# DSP_GPIO_Part4.net
KiCad netlist of a schematic drawn in Altium Designer
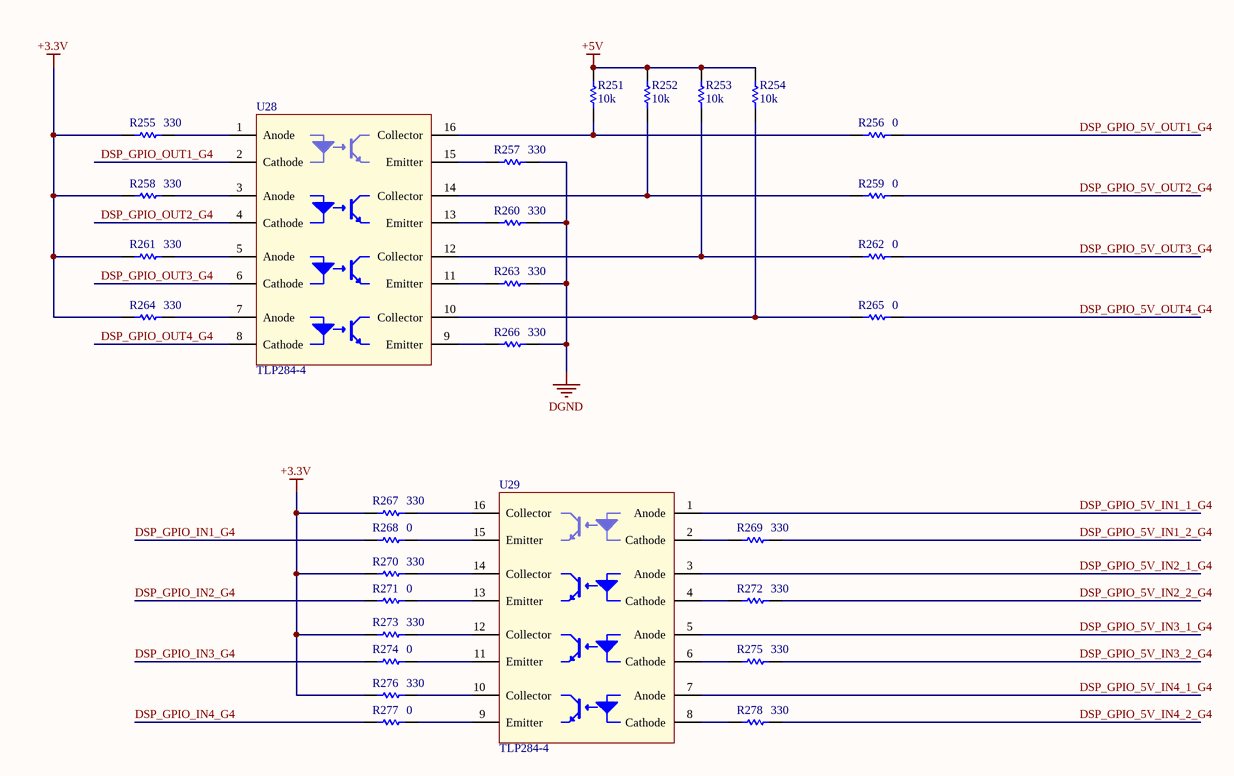
[diagram p0: DSP_GPIO_Part4.SchDoc]

(export (version "E")
  (design (tool "Eeschema 10.0.6"))
  (components
    (comp (ref "R251")
      (value "10k")
      (footprint "1608[0603]")
      (description "Resistor")
      (fields (field (name "Comment") "Res1") (field (name "PUBLISHER") "Altium Limited"))
      (libsource (lib "Miscellaneous Devices") (part "Res1"))
    )
    (comp (ref "R252")
      (value "10k")
      (footprint "1608[0603]")
      (description "Resistor")
      (fields (field (name "Comment") "Res1") (field (name "PUBLISHER") "Altium Limited"))
      (libsource (lib "Miscellaneous Devices") (part "Res1"))
    )
    (comp (ref "R253")
      (value "10k")
      (footprint "1608[0603]")
      (description "Resistor")
      (fields (field (name "Comment") "Res1") (field (name "PUBLISHER") "Altium Limited"))
      (libsource (lib "Miscellaneous Devices") (part "Res1"))
    )
    (comp (ref "R254")
      (value "10k")
      (footprint "1608[0603]")
      (description "Resistor")
      (fields (field (name "Comment") "Res1") (field (name "PUBLISHER") "Altium Limited"))
      (libsource (lib "Miscellaneous Devices") (part "Res1"))
    )
    (comp (ref "R255")
      (value "330")
      (footprint "1608[0603]")
      (description "Resistor")
      (fields (field (name "Comment") "Res1") (field (name "PUBLISHER") "Altium Limited"))
      (libsource (lib "Miscellaneous Devices") (part "Res1"))
    )
    (comp (ref "R256")
      (value "0")
      (footprint "1608[0603]")
      (description "Resistor")
      (fields (field (name "Comment") "Res1") (field (name "PUBLISHER") "Altium Limited"))
      (libsource (lib "Miscellaneous Devices") (part "Res1"))
    )
    (comp (ref "R257")
      (value "330")
      (footprint "1608[0603]")
      (description "Resistor")
      (fields (field (name "Comment") "Res1") (field (name "PUBLISHER") "Altium Limited"))
      (libsource (lib "Miscellaneous Devices") (part "Res1"))
    )
    (comp (ref "R258")
      (value "330")
      (footprint "1608[0603]")
      (description "Resistor")
      (fields (field (name "Comment") "Res1") (field (name "PUBLISHER") "Altium Limited"))
      (libsource (lib "Miscellaneous Devices") (part "Res1"))
    )
    (comp (ref "R259")
      (value "0")
      (footprint "1608[0603]")
      (description "Resistor")
      (fields (field (name "Comment") "Res1") (field (name "PUBLISHER") "Altium Limited"))
      (libsource (lib "Miscellaneous Devices") (part "Res1"))
    )
    (comp (ref "R260")
      (value "330")
      (footprint "1608[0603]")
      (description "Resistor")
      (fields (field (name "Comment") "Res1") (field (name "PUBLISHER") "Altium Limited"))
      (libsource (lib "Miscellaneous Devices") (part "Res1"))
    )
    (comp (ref "R261")
      (value "330")
      (footprint "1608[0603]")
      (description "Resistor")
      (fields (field (name "Comment") "Res1") (field (name "PUBLISHER") "Altium Limited"))
      (libsource (lib "Miscellaneous Devices") (part "Res1"))
    )
    (comp (ref "R262")
      (value "0")
      (footprint "1608[0603]")
      (description "Resistor")
      (fields (field (name "Comment") "Res1") (field (name "PUBLISHER") "Altium Limited"))
      (libsource (lib "Miscellaneous Devices") (part "Res1"))
    )
    (comp (ref "R263")
      (value "330")
      (footprint "1608[0603]")
      (description "Resistor")
      (fields (field (name "Comment") "Res1") (field (name "PUBLISHER") "Altium Limited"))
      (libsource (lib "Miscellaneous Devices") (part "Res1"))
    )
    (comp (ref "R264")
      (value "330")
      (footprint "1608[0603]")
      (description "Resistor")
      (fields (field (name "Comment") "Res1") (field (name "PUBLISHER") "Altium Limited"))
      (libsource (lib "Miscellaneous Devices") (part "Res1"))
    )
    (comp (ref "R265")
      (value "0")
      (footprint "1608[0603]")
      (description "Resistor")
      (fields (field (name "Comment") "Res1") (field (name "PUBLISHER") "Altium Limited"))
      (libsource (lib "Miscellaneous Devices") (part "Res1"))
    )
    (comp (ref "R266")
      (value "330")
      (footprint "1608[0603]")
      (description "Resistor")
      (fields (field (name "Comment") "Res1") (field (name "PUBLISHER") "Altium Limited"))
      (libsource (lib "Miscellaneous Devices") (part "Res1"))
    )
    (comp (ref "R267")
      (value "330")
      (footprint "1608[0603]")
      (description "Resistor")
      (fields (field (name "Comment") "Res1") (field (name "PUBLISHER") "Altium Limited"))
      (libsource (lib "Miscellaneous Devices") (part "Res1"))
    )
    (comp (ref "R268")
      (value "0")
      (footprint "1608[0603]")
      (description "Resistor")
      (fields (field (name "Comment") "Res1") (field (name "PUBLISHER") "Altium Limited"))
      (libsource (lib "Miscellaneous Devices") (part "Res1"))
    )
    (comp (ref "R269")
      (value "330")
      (footprint "1608[0603]")
      (description "Resistor")
      (fields (field (name "Comment") "Res1") (field (name "PUBLISHER") "Altium Limited"))
      (libsource (lib "Miscellaneous Devices") (part "Res1"))
    )
    (comp (ref "R270")
      (value "330")
      (footprint "1608[0603]")
      (description "Resistor")
      (fields (field (name "Comment") "Res1") (field (name "PUBLISHER") "Altium Limited"))
      (libsource (lib "Miscellaneous Devices") (part "Res1"))
    )
    (comp (ref "R271")
      (value "0")
      (footprint "1608[0603]")
      (description "Resistor")
      (fields (field (name "Comment") "Res1") (field (name "PUBLISHER") "Altium Limited"))
      (libsource (lib "Miscellaneous Devices") (part "Res1"))
    )
    (comp (ref "R272")
      (value "330")
      (footprint "1608[0603]")
      (description "Resistor")
      (fields (field (name "Comment") "Res1") (field (name "PUBLISHER") "Altium Limited"))
      (libsource (lib "Miscellaneous Devices") (part "Res1"))
    )
    (comp (ref "R273")
      (value "330")
      (footprint "1608[0603]")
      (description "Resistor")
      (fields (field (name "Comment") "Res1") (field (name "PUBLISHER") "Altium Limited"))
      (libsource (lib "Miscellaneous Devices") (part "Res1"))
    )
    (comp (ref "R274")
      (value "0")
      (footprint "1608[0603]")
      (description "Resistor")
      (fields (field (name "Comment") "Res1") (field (name "PUBLISHER") "Altium Limited"))
      (libsource (lib "Miscellaneous Devices") (part "Res1"))
    )
    (comp (ref "R275")
      (value "330")
      (footprint "1608[0603]")
      (description "Resistor")
      (fields (field (name "Comment") "Res1") (field (name "PUBLISHER") "Altium Limited"))
      (libsource (lib "Miscellaneous Devices") (part "Res1"))
    )
    (comp (ref "R276")
      (value "330")
      (footprint "1608[0603]")
      (description "Resistor")
      (fields (field (name "Comment") "Res1") (field (name "PUBLISHER") "Altium Limited"))
      (libsource (lib "Miscellaneous Devices") (part "Res1"))
    )
    (comp (ref "R277")
      (value "0")
      (footprint "1608[0603]")
      (description "Resistor")
      (fields (field (name "Comment") "Res1") (field (name "PUBLISHER") "Altium Limited"))
      (libsource (lib "Miscellaneous Devices") (part "Res1"))
    )
    (comp (ref "R278")
      (value "330")
      (footprint "1608[0603]")
      (description "Resistor")
      (fields (field (name "Comment") "Res1") (field (name "PUBLISHER") "Altium Limited"))
      (libsource (lib "Miscellaneous Devices") (part "Res1"))
    )
    (comp (ref "U28")
      (value "TLP284-4")
      (footprint "TLP284-4")
      (libsource (lib "DSP_FPGA_Lib") (part "TLP284-4"))
    )
    (comp (ref "U29")
      (value "TLP284-4")
      (footprint "TLP284-4")
      (libsource (lib "DSP_FPGA_Lib") (part "TLP284-4"))
    )
  )
  (nets
    (net (code "1") (name "+3.3V") (class "Default")
      (node (ref "R255") (pin "1") (pinfunction "1_1") (pintype "passive"))
      (node (ref "R258") (pin "1") (pinfunction "1_1") (pintype "passive"))
      (node (ref "R261") (pin "1") (pinfunction "1_1") (pintype "passive"))
      (node (ref "R264") (pin "1") (pinfunction "1_1") (pintype "passive"))
      (node (ref "R267") (pin "1") (pinfunction "1_1") (pintype "passive"))
      (node (ref "R270") (pin "1") (pinfunction "1_1") (pintype "passive"))
      (node (ref "R273") (pin "1") (pinfunction "1_1") (pintype "passive"))
      (node (ref "R276") (pin "1") (pinfunction "1_1") (pintype "passive"))
    )
    (net (code "2") (name "+5V") (class "Default")
      (node (ref "R251") (pin "2") (pinfunction "2_2") (pintype "passive"))
      (node (ref "R252") (pin "2") (pinfunction "2_2") (pintype "passive"))
      (node (ref "R253") (pin "2") (pinfunction "2_2") (pintype "passive"))
      (node (ref "R254") (pin "2") (pinfunction "2_2") (pintype "passive"))
    )
    (net (code "3") (name "/DSP_GPIO_5V_IN1_1_G4") (class "Default")
      (node (ref "U29") (pin "1") (pinfunction "Anode_1") (pintype "passive"))
    )
    (net (code "4") (name "/DSP_GPIO_5V_IN1_2_G4") (class "Default")
      (node (ref "R269") (pin "2") (pinfunction "2_2") (pintype "passive"))
    )
    (net (code "5") (name "/DSP_GPIO_5V_IN2_1_G4") (class "Default")
      (node (ref "U29") (pin "3") (pinfunction "Anode_3") (pintype "passive"))
    )
    (net (code "6") (name "/DSP_GPIO_5V_IN2_2_G4") (class "Default")
      (node (ref "R272") (pin "2") (pinfunction "2_2") (pintype "passive"))
    )
    (net (code "7") (name "/DSP_GPIO_5V_IN3_1_G4") (class "Default")
      (node (ref "U29") (pin "5") (pinfunction "Anode_5") (pintype "passive"))
    )
    (net (code "8") (name "/DSP_GPIO_5V_IN3_2_G4") (class "Default")
      (node (ref "R275") (pin "2") (pinfunction "2_2") (pintype "passive"))
    )
    (net (code "9") (name "/DSP_GPIO_5V_IN4_1_G4") (class "Default")
      (node (ref "U29") (pin "7") (pinfunction "Anode_7") (pintype "passive"))
    )
    (net (code "10") (name "/DSP_GPIO_5V_IN4_2_G4") (class "Default")
      (node (ref "R278") (pin "2") (pinfunction "2_2") (pintype "passive"))
    )
    (net (code "11") (name "/DSP_GPIO_5V_OUT1_G4") (class "Default")
      (node (ref "R256") (pin "2") (pinfunction "2_2") (pintype "passive"))
    )
    (net (code "12") (name "/DSP_GPIO_5V_OUT2_G4") (class "Default")
      (node (ref "R259") (pin "2") (pinfunction "2_2") (pintype "passive"))
    )
    (net (code "13") (name "/DSP_GPIO_5V_OUT3_G4") (class "Default")
      (node (ref "R262") (pin "2") (pinfunction "2_2") (pintype "passive"))
    )
    (net (code "14") (name "/DSP_GPIO_5V_OUT4_G4") (class "Default")
      (node (ref "R265") (pin "2") (pinfunction "2_2") (pintype "passive"))
    )
    (net (code "15") (name "/DSP_GPIO_IN1_G4") (class "Default")
      (node (ref "R268") (pin "1") (pinfunction "1_1") (pintype "passive"))
    )
    (net (code "16") (name "/DSP_GPIO_IN2_G4") (class "Default")
      (node (ref "R271") (pin "1") (pinfunction "1_1") (pintype "passive"))
    )
    (net (code "17") (name "/DSP_GPIO_IN3_G4") (class "Default")
      (node (ref "R274") (pin "1") (pinfunction "1_1") (pintype "passive"))
    )
    (net (code "18") (name "/DSP_GPIO_IN4_G4") (class "Default")
      (node (ref "R277") (pin "1") (pinfunction "1_1") (pintype "passive"))
    )
    (net (code "19") (name "/DSP_GPIO_OUT1_G4") (class "Default")
      (node (ref "U28") (pin "2") (pinfunction "Cathode_2") (pintype "passive"))
    )
    (net (code "20") (name "/DSP_GPIO_OUT2_G4") (class "Default")
      (node (ref "U28") (pin "4") (pinfunction "Cathode_4") (pintype "passive"))
    )
    (net (code "21") (name "/DSP_GPIO_OUT3_G4") (class "Default")
      (node (ref "U28") (pin "6") (pinfunction "Cathode_6") (pintype "passive"))
    )
    (net (code "22") (name "/DSP_GPIO_OUT4_G4") (class "Default")
      (node (ref "U28") (pin "8") (pinfunction "Cathode_8") (pintype "passive"))
    )
    (net (code "23") (name "DGND") (class "Default")
      (node (ref "R257") (pin "2") (pinfunction "2_2") (pintype "passive"))
      (node (ref "R260") (pin "2") (pinfunction "2_2") (pintype "passive"))
      (node (ref "R263") (pin "2") (pinfunction "2_2") (pintype "passive"))
      (node (ref "R266") (pin "2") (pinfunction "2_2") (pintype "passive"))
    )
    (net (code "24") (name "Net-(R251-Pad1)") (class "Default")
      (node (ref "R251") (pin "1") (pinfunction "1_1") (pintype "passive"))
      (node (ref "R256") (pin "1") (pinfunction "1_1") (pintype "passive"))
      (node (ref "U28") (pin "16") (pinfunction "Collector_16") (pintype "passive"))
    )
    (net (code "25") (name "Net-(R252-Pad1)") (class "Default")
      (node (ref "R252") (pin "1") (pinfunction "1_1") (pintype "passive"))
      (node (ref "R259") (pin "1") (pinfunction "1_1") (pintype "passive"))
      (node (ref "U28") (pin "14") (pinfunction "Collector_14") (pintype "passive"))
    )
    (net (code "26") (name "Net-(R253-Pad1)") (class "Default")
      (node (ref "R253") (pin "1") (pinfunction "1_1") (pintype "passive"))
      (node (ref "R262") (pin "1") (pinfunction "1_1") (pintype "passive"))
      (node (ref "U28") (pin "12") (pinfunction "Collector_12") (pintype "passive"))
    )
    (net (code "27") (name "Net-(R254-Pad1)") (class "Default")
      (node (ref "R254") (pin "1") (pinfunction "1_1") (pintype "passive"))
      (node (ref "R265") (pin "1") (pinfunction "1_1") (pintype "passive"))
      (node (ref "U28") (pin "10") (pinfunction "Collector_10") (pintype "passive"))
    )
    (net (code "28") (name "Net-(R255-Pad2)") (class "Default")
      (node (ref "R255") (pin "2") (pinfunction "2_2") (pintype "passive"))
      (node (ref "U28") (pin "1") (pinfunction "Anode_1") (pintype "passive"))
    )
    (net (code "29") (name "Net-(R257-Pad1)") (class "Default")
      (node (ref "R257") (pin "1") (pinfunction "1_1") (pintype "passive"))
      (node (ref "U28") (pin "15") (pinfunction "Emitter_15") (pintype "passive"))
    )
    (net (code "30") (name "Net-(R258-Pad2)") (class "Default")
      (node (ref "R258") (pin "2") (pinfunction "2_2") (pintype "passive"))
      (node (ref "U28") (pin "3") (pinfunction "Anode_3") (pintype "passive"))
    )
    (net (code "31") (name "Net-(R260-Pad1)") (class "Default")
      (node (ref "R260") (pin "1") (pinfunction "1_1") (pintype "passive"))
      (node (ref "U28") (pin "13") (pinfunction "Emitter_13") (pintype "passive"))
    )
    (net (code "32") (name "Net-(R261-Pad2)") (class "Default")
      (node (ref "R261") (pin "2") (pinfunction "2_2") (pintype "passive"))
      (node (ref "U28") (pin "5") (pinfunction "Anode_5") (pintype "passive"))
    )
    (net (code "33") (name "Net-(R263-Pad1)") (class "Default")
      (node (ref "R263") (pin "1") (pinfunction "1_1") (pintype "passive"))
      (node (ref "U28") (pin "11") (pinfunction "Emitter_11") (pintype "passive"))
    )
    (net (code "34") (name "Net-(R264-Pad2)") (class "Default")
      (node (ref "R264") (pin "2") (pinfunction "2_2") (pintype "passive"))
      (node (ref "U28") (pin "7") (pinfunction "Anode_7") (pintype "passive"))
    )
    (net (code "35") (name "Net-(R266-Pad1)") (class "Default")
      (node (ref "R266") (pin "1") (pinfunction "1_1") (pintype "passive"))
      (node (ref "U28") (pin "9") (pinfunction "Emitter_9") (pintype "passive"))
    )
    (net (code "36") (name "Net-(R267-Pad2)") (class "Default")
      (node (ref "R267") (pin "2") (pinfunction "2_2") (pintype "passive"))
      (node (ref "U29") (pin "16") (pinfunction "Collector_16") (pintype "passive"))
    )
    (net (code "37") (name "Net-(R268-Pad2)") (class "Default")
      (node (ref "R268") (pin "2") (pinfunction "2_2") (pintype "passive"))
      (node (ref "U29") (pin "15") (pinfunction "Emitter_15") (pintype "passive"))
    )
    (net (code "38") (name "Net-(R269-Pad1)") (class "Default")
      (node (ref "R269") (pin "1") (pinfunction "1_1") (pintype "passive"))
      (node (ref "U29") (pin "2") (pinfunction "Cathode_2") (pintype "passive"))
    )
    (net (code "39") (name "Net-(R270-Pad2)") (class "Default")
      (node (ref "R270") (pin "2") (pinfunction "2_2") (pintype "passive"))
      (node (ref "U29") (pin "14") (pinfunction "Collector_14") (pintype "passive"))
    )
    (net (code "40") (name "Net-(R271-Pad2)") (class "Default")
      (node (ref "R271") (pin "2") (pinfunction "2_2") (pintype "passive"))
      (node (ref "U29") (pin "13") (pinfunction "Emitter_13") (pintype "passive"))
    )
    (net (code "41") (name "Net-(R272-Pad1)") (class "Default")
      (node (ref "R272") (pin "1") (pinfunction "1_1") (pintype "passive"))
      (node (ref "U29") (pin "4") (pinfunction "Cathode_4") (pintype "passive"))
    )
    (net (code "42") (name "Net-(R273-Pad2)") (class "Default")
      (node (ref "R273") (pin "2") (pinfunction "2_2") (pintype "passive"))
      (node (ref "U29") (pin "12") (pinfunction "Collector_12") (pintype "passive"))
    )
    (net (code "43") (name "Net-(R274-Pad2)") (class "Default")
      (node (ref "R274") (pin "2") (pinfunction "2_2") (pintype "passive"))
      (node (ref "U29") (pin "11") (pinfunction "Emitter_11") (pintype "passive"))
    )
    (net (code "44") (name "Net-(R275-Pad1)") (class "Default")
      (node (ref "R275") (pin "1") (pinfunction "1_1") (pintype "passive"))
      (node (ref "U29") (pin "6") (pinfunction "Cathode_6") (pintype "passive"))
    )
    (net (code "45") (name "Net-(R276-Pad2)") (class "Default")
      (node (ref "R276") (pin "2") (pinfunction "2_2") (pintype "passive"))
      (node (ref "U29") (pin "10") (pinfunction "Collector_10") (pintype "passive"))
    )
    (net (code "46") (name "Net-(R277-Pad2)") (class "Default")
      (node (ref "R277") (pin "2") (pinfunction "2_2") (pintype "passive"))
      (node (ref "U29") (pin "9") (pinfunction "Emitter_9") (pintype "passive"))
    )
    (net (code "47") (name "Net-(R278-Pad1)") (class "Default")
      (node (ref "R278") (pin "1") (pinfunction "1_1") (pintype "passive"))
      (node (ref "U29") (pin "8") (pinfunction "Cathode_8") (pintype "passive"))
    )
  )
)
